# Control_Acceso_Doble_Faz.net
KiCad netlist of a schematic drawn in EAGLE
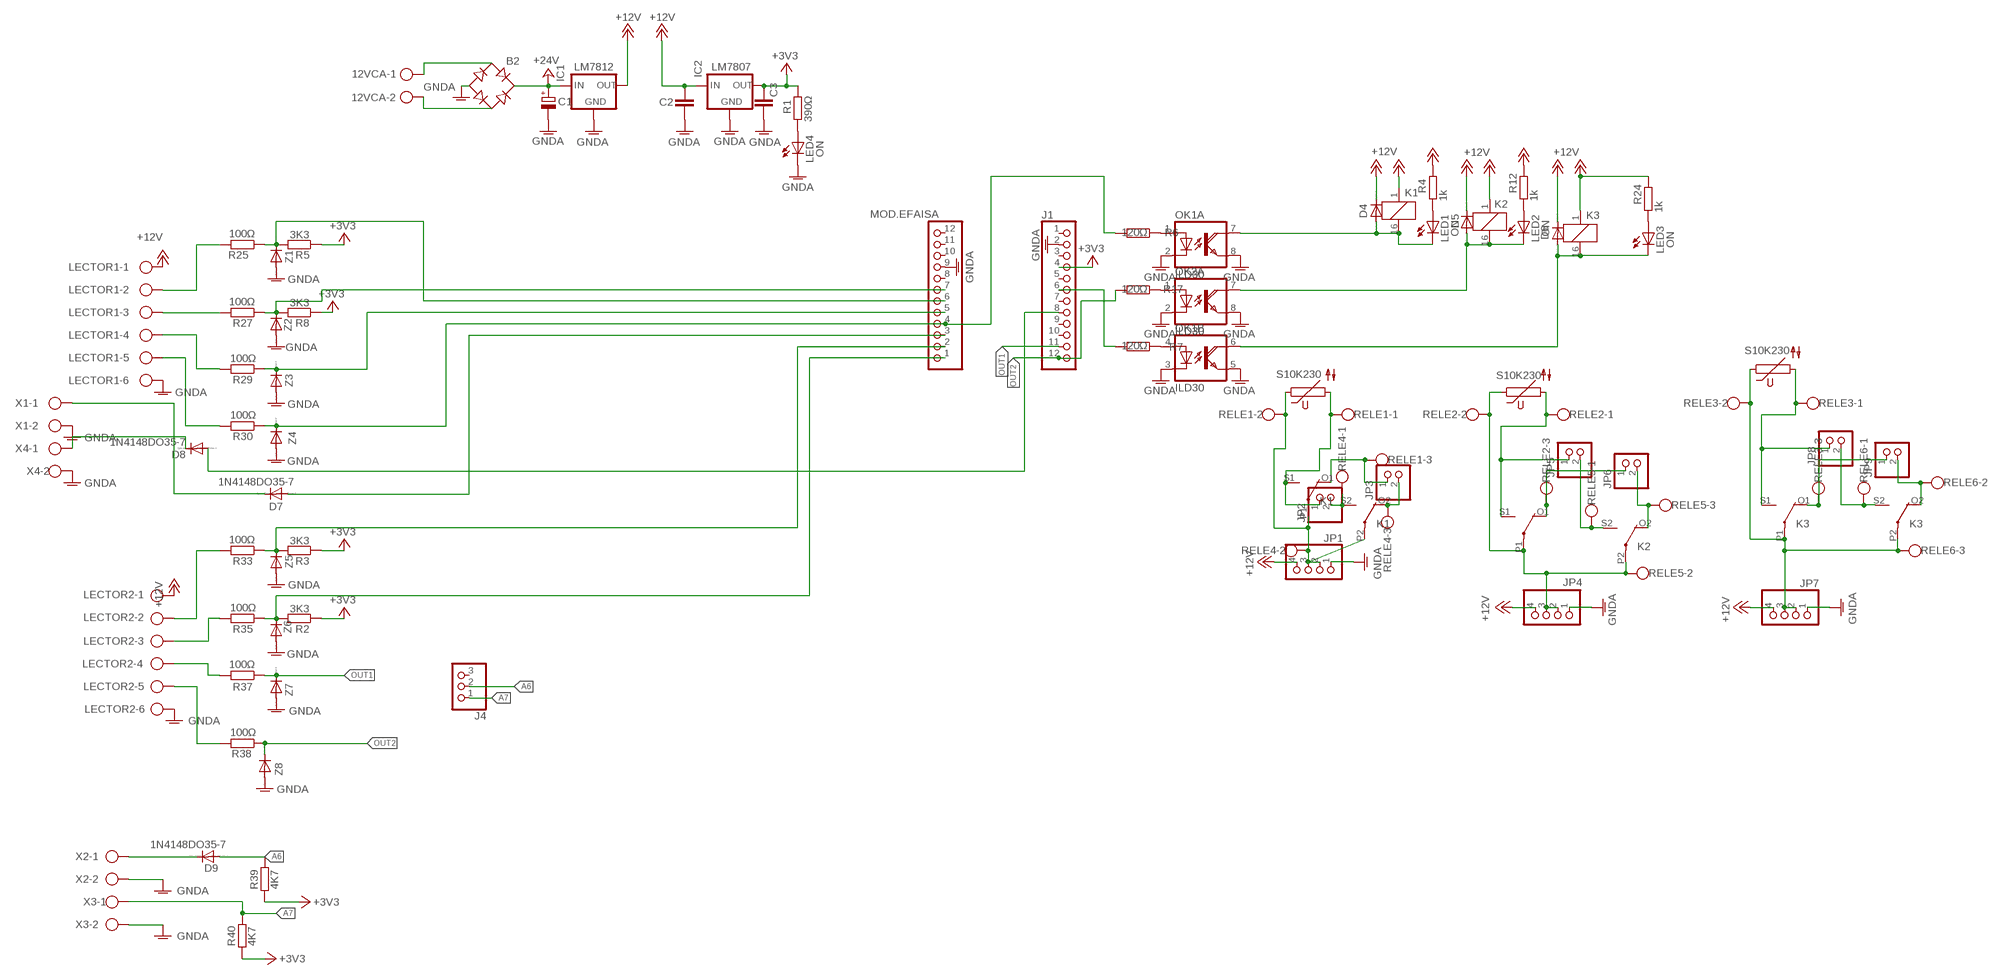
[diagram p0: schematic, sheet 1]

(export (version "E")
  (design (tool "Eeschema 10.0.6"))
  (components
    (comp (ref "12VCA")
      (value "W237-102")
      (footprint "eagle-import:W237-102")
      (fields (field (name "MPN") "237-102"))
      (libsource (lib "eagle-import") (part "W237-102"))
    )
    (comp (ref "B2")
      (value "RB1A")
      (footprint "eagle-import:RB1A")
      (libsource (lib "eagle-import") (part "RB1A"))
    )
    (comp (ref "C1")
      (value "CPOL-EUE5-13")
      (footprint "eagle-import:E5-13")
      (libsource (lib "eagle-import") (part "CPOL-EUE5-13"))
    )
    (comp (ref "C2")
      (value "C-EU050-024X044")
      (footprint "eagle-import:C050-024X044")
      (libsource (lib "eagle-import") (part "C-EU050-024X044"))
    )
    (comp (ref "C3")
      (value "C-EU050-024X044")
      (footprint "eagle-import:C050-024X044")
      (libsource (lib "eagle-import") (part "C-EU050-024X044"))
    )
    (comp (ref "D4")
      (value "1N4148DO35-7")
      (footprint "eagle-import:DO35-7")
      (libsource (lib "eagle-import") (part "1N4148DO35-7"))
    )
    (comp (ref "D5")
      (value "1N4148DO35-7")
      (footprint "eagle-import:DO35-7")
      (libsource (lib "eagle-import") (part "1N4148DO35-7"))
    )
    (comp (ref "D6")
      (value "1N4148DO35-7")
      (footprint "eagle-import:DO35-7")
      (libsource (lib "eagle-import") (part "1N4148DO35-7"))
    )
    (comp (ref "D7")
      (value "1N4148DO35-7")
      (footprint "eagle-import:DO35-7")
      (libsource (lib "eagle-import") (part "1N4148DO35-7"))
    )
    (comp (ref "D8")
      (value "1N4148DO35-7")
      (footprint "eagle-import:DO35-7")
      (libsource (lib "eagle-import") (part "1N4148DO35-7"))
    )
    (comp (ref "D9")
      (value "1N4148DO35-7")
      (footprint "eagle-import:DO35-7")
      (libsource (lib "eagle-import") (part "1N4148DO35-7"))
    )
    (comp (ref "IC1")
      (value "LM7812")
      (footprint "eagle-import:78XXS")
      (libsource (lib "eagle-import") (part "78XXS"))
    )
    (comp (ref "IC2")
      (value "LM7807")
      (footprint "eagle-import:78XXS")
      (libsource (lib "eagle-import") (part "78XXS"))
    )
    (comp (ref "J1")
      (value "PINHD-1X12")
      (footprint "eagle-import:1X12")
      (libsource (lib "eagle-import") (part "PINHD-1X12"))
    )
    (comp (ref "J4")
      (value "PINHD-1X3")
      (footprint "eagle-import:1X03")
      (libsource (lib "eagle-import") (part "PINHD-1X3"))
    )
    (comp (ref "JP1")
      (value "PINHD-1X4")
      (footprint "eagle-import:1X04")
      (libsource (lib "eagle-import") (part "PINHD-1X4"))
    )
    (comp (ref "JP2")
      (value "PINHD-1X2")
      (footprint "eagle-import:1X02")
      (libsource (lib "eagle-import") (part "PINHD-1X2"))
    )
    (comp (ref "JP3")
      (value "PINHD-1X2")
      (footprint "eagle-import:1X02")
      (libsource (lib "eagle-import") (part "PINHD-1X2"))
    )
    (comp (ref "JP4")
      (value "PINHD-1X4")
      (footprint "eagle-import:1X04")
      (libsource (lib "eagle-import") (part "PINHD-1X4"))
    )
    (comp (ref "JP5")
      (value "PINHD-1X2")
      (footprint "eagle-import:1X02")
      (libsource (lib "eagle-import") (part "PINHD-1X2"))
    )
    (comp (ref "JP6")
      (value "PINHD-1X2")
      (footprint "eagle-import:1X02")
      (libsource (lib "eagle-import") (part "PINHD-1X2"))
    )
    (comp (ref "JP7")
      (value "PINHD-1X4")
      (footprint "eagle-import:1X04")
      (libsource (lib "eagle-import") (part "PINHD-1X4"))
    )
    (comp (ref "JP8")
      (value "PINHD-1X2")
      (footprint "eagle-import:1X02")
      (libsource (lib "eagle-import") (part "PINHD-1X2"))
    )
    (comp (ref "JP9")
      (value "PINHD-1X2")
      (footprint "eagle-import:1X02")
      (libsource (lib "eagle-import") (part "PINHD-1X2"))
    )
    (comp (ref "K1")
      (value "351")
      (footprint "eagle-import:351")
      (libsource (lib "eagle-import") (part "351"))
    )
    (comp (ref "K2")
      (value "351")
      (footprint "eagle-import:351")
      (libsource (lib "eagle-import") (part "351"))
    )
    (comp (ref "K3")
      (value "351")
      (footprint "eagle-import:351")
      (libsource (lib "eagle-import") (part "351"))
    )
    (comp (ref "LECTOR1")
      (value "W237-6")
      (footprint "eagle-import:W237-6")
      (libsource (lib "eagle-import") (part "W237-6"))
    )
    (comp (ref "LECTOR2")
      (value "W237-6")
      (footprint "eagle-import:W237-6")
      (libsource (lib "eagle-import") (part "W237-6"))
    )
    (comp (ref "LED1")
      (value "ON")
      (footprint "eagle-import:LED3MM")
      (libsource (lib "eagle-import") (part "LED3MM"))
    )
    (comp (ref "LED2")
      (value "ON")
      (footprint "eagle-import:LED3MM")
      (libsource (lib "eagle-import") (part "LED3MM"))
    )
    (comp (ref "LED3")
      (value "ON")
      (footprint "eagle-import:LED3MM")
      (libsource (lib "eagle-import") (part "LED3MM"))
    )
    (comp (ref "LED4")
      (value "ON")
      (footprint "eagle-import:LED3MM")
      (libsource (lib "eagle-import") (part "LED3MM"))
    )
    (comp (ref "MOD.EFAISA")
      (value "PINHD-1X12")
      (footprint "eagle-import:1X12")
      (libsource (lib "eagle-import") (part "PINHD-1X12"))
    )
    (comp (ref "OK1")
      (value "ILD30")
      (footprint "eagle-import:DIL08")
      (fields (field (name "MF") "VISHAY/TELEFUNKEN"))
      (libsource (lib "eagle-import") (part "ILD30"))
    )
    (comp (ref "OK2")
      (value "ILD30")
      (footprint "eagle-import:DIL08")
      (fields (field (name "MF") "VISHAY/TELEFUNKEN"))
      (libsource (lib "eagle-import") (part "ILD30"))
    )
    (comp (ref "R1")
      (value "390Ω")
      (footprint "eagle-import:0204_7")
      (libsource (lib "eagle-import") (part "R-EU_0204/7"))
    )
    (comp (ref "R2")
      (value "3K3")
      (footprint "eagle-import:0204_7")
      (libsource (lib "eagle-import") (part "R-EU_0204/7"))
    )
    (comp (ref "R3")
      (value "3K3")
      (footprint "eagle-import:0204_7")
      (libsource (lib "eagle-import") (part "R-EU_0204/7"))
    )
    (comp (ref "R4")
      (value "1k")
      (footprint "eagle-import:0204_7")
      (libsource (lib "eagle-import") (part "R-EU_0204/7"))
    )
    (comp (ref "R5")
      (value "3K3")
      (footprint "eagle-import:0204_7")
      (libsource (lib "eagle-import") (part "R-EU_0204/7"))
    )
    (comp (ref "R6")
      (value "120Ω")
      (footprint "eagle-import:0204_7")
      (libsource (lib "eagle-import") (part "R-EU_0204/7"))
    )
    (comp (ref "R7")
      (value "120Ω")
      (footprint "eagle-import:0204_7")
      (libsource (lib "eagle-import") (part "R-EU_0204/7"))
    )
    (comp (ref "R8")
      (value "3K3")
      (footprint "eagle-import:0204_7")
      (libsource (lib "eagle-import") (part "R-EU_0204/7"))
    )
    (comp (ref "R12")
      (value "1k")
      (footprint "eagle-import:0204_7")
      (libsource (lib "eagle-import") (part "R-EU_0204/7"))
    )
    (comp (ref "R17")
      (value "120Ω")
      (footprint "eagle-import:0204_7")
      (libsource (lib "eagle-import") (part "R-EU_0204/7"))
    )
    (comp (ref "R24")
      (value "1k")
      (footprint "eagle-import:0204_7")
      (libsource (lib "eagle-import") (part "R-EU_0204/7"))
    )
    (comp (ref "R25")
      (value "100Ω")
      (footprint "eagle-import:0204_7")
      (libsource (lib "eagle-import") (part "R-EU_0204/7"))
    )
    (comp (ref "R27")
      (value "100Ω")
      (footprint "eagle-import:0204_7")
      (libsource (lib "eagle-import") (part "R-EU_0204/7"))
    )
    (comp (ref "R29")
      (value "100Ω")
      (footprint "eagle-import:0204_7")
      (libsource (lib "eagle-import") (part "R-EU_0204/7"))
    )
    (comp (ref "R30")
      (value "100Ω")
      (footprint "eagle-import:0204_7")
      (libsource (lib "eagle-import") (part "R-EU_0204/7"))
    )
    (comp (ref "R33")
      (value "100Ω")
      (footprint "eagle-import:0204_7")
      (libsource (lib "eagle-import") (part "R-EU_0204/7"))
    )
    (comp (ref "R35")
      (value "100Ω")
      (footprint "eagle-import:0204_7")
      (libsource (lib "eagle-import") (part "R-EU_0204/7"))
    )
    (comp (ref "R37")
      (value "100Ω")
      (footprint "eagle-import:0204_7")
      (libsource (lib "eagle-import") (part "R-EU_0204/7"))
    )
    (comp (ref "R38")
      (value "100Ω")
      (footprint "eagle-import:0204_7")
      (libsource (lib "eagle-import") (part "R-EU_0204/7"))
    )
    (comp (ref "R39")
      (value "4K7")
      (footprint "eagle-import:0204_7")
      (libsource (lib "eagle-import") (part "R-EU_0204/7"))
    )
    (comp (ref "R40")
      (value "4K7")
      (footprint "eagle-import:0204_7")
      (libsource (lib "eagle-import") (part "R-EU_0204/7"))
    )
    (comp (ref "RELE1")
      (value "W237-103")
      (footprint "eagle-import:W237-103")
      (fields (field (name "MPN") "237-103"))
      (libsource (lib "eagle-import") (part "W237-103"))
    )
    (comp (ref "RELE2")
      (value "W237-103")
      (footprint "eagle-import:W237-103")
      (fields (field (name "MPN") "237-103"))
      (libsource (lib "eagle-import") (part "W237-103"))
    )
    (comp (ref "RELE3")
      (value "W237-103")
      (footprint "eagle-import:W237-103")
      (fields (field (name "MPN") "237-103"))
      (libsource (lib "eagle-import") (part "W237-103"))
    )
    (comp (ref "RELE4")
      (value "W237-103")
      (footprint "eagle-import:W237-103")
      (fields (field (name "MPN") "237-103"))
      (libsource (lib "eagle-import") (part "W237-103"))
    )
    (comp (ref "RELE5")
      (value "W237-103")
      (footprint "eagle-import:W237-103")
      (fields (field (name "MPN") "237-103"))
      (libsource (lib "eagle-import") (part "W237-103"))
    )
    (comp (ref "RELE6")
      (value "W237-103")
      (footprint "eagle-import:W237-103")
      (fields (field (name "MPN") "237-103"))
      (libsource (lib "eagle-import") (part "W237-103"))
    )
    (comp (ref "V1")
      (value "S10K230")
      (footprint "eagle-import:S10K230")
      (libsource (lib "eagle-import") (part "S10K230"))
    )
    (comp (ref "V2")
      (value "S10K230")
      (footprint "eagle-import:S10K230")
      (libsource (lib "eagle-import") (part "S10K230"))
    )
    (comp (ref "V3")
      (value "S10K230")
      (footprint "eagle-import:S10K230")
      (libsource (lib "eagle-import") (part "S10K230"))
    )
    (comp (ref "X1")
      (value "W237-102")
      (footprint "eagle-import:W237-102")
      (fields (field (name "MPN") "237-102"))
      (libsource (lib "eagle-import") (part "W237-102"))
    )
    (comp (ref "X2")
      (value "W237-102")
      (footprint "eagle-import:W237-102")
      (fields (field (name "MPN") "237-102"))
      (libsource (lib "eagle-import") (part "W237-102"))
    )
    (comp (ref "X3")
      (value "W237-102")
      (footprint "eagle-import:W237-102")
      (fields (field (name "MPN") "237-102"))
      (libsource (lib "eagle-import") (part "W237-102"))
    )
    (comp (ref "X4")
      (value "W237-102")
      (footprint "eagle-import:W237-102")
      (fields (field (name "MPN") "237-102"))
      (libsource (lib "eagle-import") (part "W237-102"))
    )
    (comp (ref "Z1")
      (value "ZENNER 4V7")
      (footprint "eagle-import:DO35-7")
      (libsource (lib "eagle-import") (part "1N4148DO35-7"))
    )
    (comp (ref "Z2")
      (value "ZENNER 4V7")
      (footprint "eagle-import:DO35-7")
      (libsource (lib "eagle-import") (part "1N4148DO35-7"))
    )
    (comp (ref "Z3")
      (value "ZENNER 4V7")
      (footprint "eagle-import:DO35-7")
      (libsource (lib "eagle-import") (part "1N4148DO35-7"))
    )
    (comp (ref "Z4")
      (value "ZENNER 4V7")
      (footprint "eagle-import:DO35-7")
      (libsource (lib "eagle-import") (part "1N4148DO35-7"))
    )
    (comp (ref "Z5")
      (value "ZENNER 4V7")
      (footprint "eagle-import:DO35-7")
      (libsource (lib "eagle-import") (part "1N4148DO35-7"))
    )
    (comp (ref "Z6")
      (value "ZENNER 4V7")
      (footprint "eagle-import:DO35-7")
      (libsource (lib "eagle-import") (part "1N4148DO35-7"))
    )
    (comp (ref "Z7")
      (value "ZENNER 4V7")
      (footprint "eagle-import:DO35-7")
      (libsource (lib "eagle-import") (part "1N4148DO35-7"))
    )
    (comp (ref "Z8")
      (value "ZENNER 4V7")
      (footprint "eagle-import:DO35-7")
      (libsource (lib "eagle-import") (part "1N4148DO35-7"))
    )
  )
  (nets
    (net (code "1") (name "+3V3") (class "Default")
      (node (ref "C3") (pin "1") (pinfunction "1_1") (pintype "passive"))
      (node (ref "IC2") (pin "OUT") (pinfunction "OUT_OUT") (pintype "passive"))
      (node (ref "J1") (pin "4") (pinfunction "4_4") (pintype "passive"))
      (node (ref "R1") (pin "2") (pinfunction "2_2") (pintype "passive"))
      (node (ref "R2") (pin "1") (pinfunction "1_1") (pintype "passive"))
      (node (ref "R3") (pin "1") (pinfunction "1_1") (pintype "passive"))
      (node (ref "R39") (pin "1") (pinfunction "1_1") (pintype "passive"))
      (node (ref "R40") (pin "1") (pinfunction "1_1") (pintype "passive"))
      (node (ref "R5") (pin "1") (pinfunction "1_1") (pintype "passive"))
      (node (ref "R8") (pin "1") (pinfunction "1_1") (pintype "passive"))
    )
    (net (code "2") (name "+12V") (class "Default")
      (node (ref "C2") (pin "1") (pinfunction "1_1") (pintype "passive"))
      (node (ref "D4") (pin "C") (pinfunction "C_C") (pintype "passive"))
      (node (ref "D5") (pin "C") (pinfunction "C_C") (pintype "passive"))
      (node (ref "D6") (pin "C") (pinfunction "C_C") (pintype "passive"))
      (node (ref "IC1") (pin "OUT") (pinfunction "OUT_OUT") (pintype "passive"))
      (node (ref "IC2") (pin "IN") (pinfunction "IN_IN") (pintype "input"))
      (node (ref "JP1") (pin "4") (pinfunction "4_4") (pintype "passive"))
      (node (ref "JP4") (pin "4") (pinfunction "4_4") (pintype "passive"))
      (node (ref "JP7") (pin "4") (pinfunction "4_4") (pintype "passive"))
      (node (ref "K1") (pin "1") (pinfunction "1_1") (pintype "passive"))
      (node (ref "K2") (pin "1") (pinfunction "1_1") (pintype "passive"))
      (node (ref "K3") (pin "1") (pinfunction "1_1") (pintype "passive"))
      (node (ref "LECTOR1") (pin "1") (pinfunction "KL_1") (pintype "passive"))
      (node (ref "LECTOR2") (pin "1") (pinfunction "KL_1") (pintype "passive"))
      (node (ref "R12") (pin "2") (pinfunction "2_2") (pintype "passive"))
      (node (ref "R24") (pin "2") (pinfunction "2_2") (pintype "passive"))
      (node (ref "R4") (pin "2") (pinfunction "2_2") (pintype "passive"))
    )
    (net (code "3") (name "+24V") (class "Default")
      (node (ref "B2") (pin "+") (pinfunction "+_+") (pintype "passive"))
      (node (ref "C1") (pin "+") (pinfunction "+_+") (pintype "passive"))
      (node (ref "IC1") (pin "IN") (pinfunction "IN_IN") (pintype "input"))
    )
    (net (code "4") (name "A6") (class "Default")
      (node (ref "D9") (pin "A") (pinfunction "A_A") (pintype "passive"))
      (node (ref "J4") (pin "2") (pinfunction "2_2") (pintype "passive"))
      (node (ref "R39") (pin "2") (pinfunction "2_2") (pintype "passive"))
    )
    (net (code "5") (name "A7") (class "Default")
      (node (ref "J4") (pin "1") (pinfunction "1_1") (pintype "passive"))
      (node (ref "R40") (pin "2") (pinfunction "2_2") (pintype "passive"))
      (node (ref "X3") (pin "1") (pinfunction "KL_1") (pintype "passive"))
    )
    (net (code "6") (name "GNDA") (class "Default")
      (node (ref "B2") (pin "-") (pinfunction "-_-") (pintype "passive"))
      (node (ref "C1") (pin "-") (pinfunction "-_-") (pintype "passive"))
      (node (ref "C2") (pin "2") (pinfunction "2_2") (pintype "passive"))
      (node (ref "C3") (pin "2") (pinfunction "2_2") (pintype "passive"))
      (node (ref "IC1") (pin "GND") (pinfunction "GND_GND") (pintype "input"))
      (node (ref "IC2") (pin "GND") (pinfunction "GND_GND") (pintype "input"))
      (node (ref "J1") (pin "2") (pinfunction "2_2") (pintype "passive"))
      (node (ref "JP1") (pin "1") (pinfunction "1_1") (pintype "passive"))
      (node (ref "JP4") (pin "1") (pinfunction "1_1") (pintype "passive"))
      (node (ref "JP7") (pin "1") (pinfunction "1_1") (pintype "passive"))
      (node (ref "LECTOR1") (pin "6") (pinfunction "KL_6") (pintype "passive"))
      (node (ref "LECTOR2") (pin "6") (pinfunction "KL_6") (pintype "passive"))
      (node (ref "LED4") (pin "K") (pinfunction "C_K") (pintype "passive"))
      (node (ref "MOD.EFAISA") (pin "9") (pinfunction "9_9") (pintype "passive"))
      (node (ref "OK1") (pin "2") (pinfunction "C_2") (pintype "passive"))
      (node (ref "OK1") (pin "3") (pinfunction "C_3") (pintype "passive"))
      (node (ref "OK1") (pin "5") (pinfunction "EMI_5") (pintype "passive"))
      (node (ref "OK1") (pin "8") (pinfunction "EMI_8") (pintype "passive"))
      (node (ref "OK2") (pin "2") (pinfunction "C_2") (pintype "passive"))
      (node (ref "OK2") (pin "8") (pinfunction "EMI_8") (pintype "passive"))
      (node (ref "X1") (pin "2") (pinfunction "KL_2") (pintype "passive"))
      (node (ref "X2") (pin "2") (pinfunction "KL_2") (pintype "passive"))
      (node (ref "X3") (pin "2") (pinfunction "KL_2") (pintype "passive"))
      (node (ref "X4") (pin "2") (pinfunction "KL_2") (pintype "passive"))
      (node (ref "Z1") (pin "A") (pinfunction "A_A") (pintype "passive"))
      (node (ref "Z2") (pin "A") (pinfunction "A_A") (pintype "passive"))
      (node (ref "Z3") (pin "A") (pinfunction "A_A") (pintype "passive"))
      (node (ref "Z4") (pin "A") (pinfunction "A_A") (pintype "passive"))
      (node (ref "Z5") (pin "A") (pinfunction "A_A") (pintype "passive"))
      (node (ref "Z6") (pin "A") (pinfunction "A_A") (pintype "passive"))
      (node (ref "Z7") (pin "A") (pinfunction "A_A") (pintype "passive"))
      (node (ref "Z8") (pin "A") (pinfunction "A_A") (pintype "passive"))
    )
    (net (code "7") (name "Net-(12VCAA-KL)") (class "Default")
      (node (ref "12VCA") (pin "1") (pinfunction "KL_1") (pintype "passive"))
      (node (ref "B2") (pin "AC1") (pinfunction "AC1_AC1") (pintype "passive"))
    )
    (net (code "8") (name "Net-(12VCAB-KL)") (class "Default")
      (node (ref "12VCA") (pin "2") (pinfunction "KL_2") (pintype "passive"))
      (node (ref "B2") (pin "AC2") (pinfunction "AC2_AC2") (pintype "passive"))
    )
    (net (code "9") (name "Net-(D7-PadA)") (class "Default")
      (node (ref "D7") (pin "A") (pinfunction "A_A") (pintype "passive"))
      (node (ref "MOD.EFAISA") (pin "3") (pinfunction "3_3") (pintype "passive"))
    )
    (net (code "10") (name "Net-(D8-PadA)") (class "Default")
      (node (ref "D8") (pin "A") (pinfunction "A_A") (pintype "passive"))
      (node (ref "J1") (pin "8") (pinfunction "8_8") (pintype "passive"))
    )
    (net (code "11") (name "Net-(J1-Pad6)") (class "Default")
      (node (ref "J1") (pin "6") (pinfunction "6_6") (pintype "passive"))
      (node (ref "R7") (pin "2") (pinfunction "2_2") (pintype "passive"))
    )
    (net (code "12") (name "Net-(K1A-2)") (class "Default")
      (node (ref "D4") (pin "A") (pinfunction "A_A") (pintype "passive"))
      (node (ref "K1") (pin "16") (pinfunction "2_16") (pintype "passive"))
      (node (ref "LED1") (pin "K") (pinfunction "C_K") (pintype "passive"))
      (node (ref "OK1") (pin "7") (pinfunction "COL_7") (pintype "passive"))
    )
    (net (code "13") (name "Net-(K1B-O)") (class "Default")
      (node (ref "JP3") (pin "1") (pinfunction "1_1") (pintype "passive"))
      (node (ref "K1") (pin "O1") (pinfunction "O_O1") (pintype "passive"))
      (node (ref "RELE1") (pin "3") (pinfunction "KL_3") (pintype "passive"))
    )
    (net (code "14") (name "Net-(K1B-P)") (class "Default")
      (node (ref "JP1") (pin "2") (pinfunction "2_2") (pintype "passive"))
      (node (ref "JP1") (pin "3") (pinfunction "3_3") (pintype "passive"))
      (node (ref "K1") (pin "P1") (pinfunction "P_P1") (pintype "passive"))
      (node (ref "K1") (pin "P2") (pinfunction "P_P2") (pintype "passive"))
      (node (ref "RELE1") (pin "2") (pinfunction "KL_2") (pintype "passive"))
      (node (ref "RELE4") (pin "2") (pinfunction "KL_2") (pintype "passive"))
      (node (ref "V1") (pin "1") (pinfunction "1_1") (pintype "passive"))
    )
    (net (code "15") (name "Net-(K1B-S)") (class "Default")
      (node (ref "JP2") (pin "1") (pinfunction "1_1") (pintype "passive"))
      (node (ref "K1") (pin "S1") (pinfunction "S_S1") (pintype "passive"))
      (node (ref "RELE1") (pin "1") (pinfunction "KL_1") (pintype "passive"))
      (node (ref "V1") (pin "2") (pinfunction "2_2") (pintype "passive"))
    )
    (net (code "16") (name "Net-(K1C-O)") (class "Default")
      (node (ref "JP3") (pin "2") (pinfunction "2_2") (pintype "passive"))
      (node (ref "K1") (pin "O2") (pinfunction "O_O2") (pintype "passive"))
      (node (ref "RELE4") (pin "3") (pinfunction "KL_3") (pintype "passive"))
    )
    (net (code "17") (name "Net-(K1C-S)") (class "Default")
      (node (ref "JP2") (pin "2") (pinfunction "2_2") (pintype "passive"))
      (node (ref "K1") (pin "S2") (pinfunction "S_S2") (pintype "passive"))
      (node (ref "RELE4") (pin "1") (pinfunction "KL_1") (pintype "passive"))
    )
    (net (code "18") (name "Net-(K2A-2)") (class "Default")
      (node (ref "D5") (pin "A") (pinfunction "A_A") (pintype "passive"))
      (node (ref "K2") (pin "16") (pinfunction "2_16") (pintype "passive"))
      (node (ref "LED2") (pin "K") (pinfunction "C_K") (pintype "passive"))
      (node (ref "OK2") (pin "7") (pinfunction "COL_7") (pintype "passive"))
    )
    (net (code "19") (name "Net-(K2B-O)") (class "Default")
      (node (ref "JP6") (pin "1") (pinfunction "1_1") (pintype "passive"))
      (node (ref "K2") (pin "O1") (pinfunction "O_O1") (pintype "passive"))
      (node (ref "RELE2") (pin "3") (pinfunction "KL_3") (pintype "passive"))
    )
    (net (code "20") (name "Net-(K2B-P)") (class "Default")
      (node (ref "JP4") (pin "2") (pinfunction "2_2") (pintype "passive"))
      (node (ref "JP4") (pin "3") (pinfunction "3_3") (pintype "passive"))
      (node (ref "K2") (pin "P1") (pinfunction "P_P1") (pintype "passive"))
      (node (ref "K2") (pin "P2") (pinfunction "P_P2") (pintype "passive"))
      (node (ref "RELE2") (pin "2") (pinfunction "KL_2") (pintype "passive"))
      (node (ref "RELE5") (pin "2") (pinfunction "KL_2") (pintype "passive"))
      (node (ref "V2") (pin "1") (pinfunction "1_1") (pintype "passive"))
    )
    (net (code "21") (name "Net-(K2B-S)") (class "Default")
      (node (ref "JP5") (pin "1") (pinfunction "1_1") (pintype "passive"))
      (node (ref "K2") (pin "S1") (pinfunction "S_S1") (pintype "passive"))
      (node (ref "RELE2") (pin "1") (pinfunction "KL_1") (pintype "passive"))
      (node (ref "V2") (pin "2") (pinfunction "2_2") (pintype "passive"))
    )
    (net (code "22") (name "Net-(K2C-O)") (class "Default")
      (node (ref "JP6") (pin "2") (pinfunction "2_2") (pintype "passive"))
      (node (ref "K2") (pin "O2") (pinfunction "O_O2") (pintype "passive"))
      (node (ref "RELE5") (pin "3") (pinfunction "KL_3") (pintype "passive"))
    )
    (net (code "23") (name "Net-(K2C-S)") (class "Default")
      (node (ref "JP5") (pin "2") (pinfunction "2_2") (pintype "passive"))
      (node (ref "K2") (pin "S2") (pinfunction "S_S2") (pintype "passive"))
      (node (ref "RELE5") (pin "1") (pinfunction "KL_1") (pintype "passive"))
    )
    (net (code "24") (name "Net-(K3A-2)") (class "Default")
      (node (ref "D6") (pin "A") (pinfunction "A_A") (pintype "passive"))
      (node (ref "K3") (pin "16") (pinfunction "2_16") (pintype "passive"))
      (node (ref "LED3") (pin "K") (pinfunction "C_K") (pintype "passive"))
      (node (ref "OK1") (pin "6") (pinfunction "COL_6") (pintype "passive"))
    )
    (net (code "25") (name "Net-(K3B-O)") (class "Default")
      (node (ref "JP9") (pin "1") (pinfunction "1_1") (pintype "passive"))
      (node (ref "K3") (pin "O1") (pinfunction "O_O1") (pintype "passive"))
      (node (ref "RELE3") (pin "3") (pinfunction "KL_3") (pintype "passive"))
    )
    (net (code "26") (name "Net-(K3B-P)") (class "Default")
      (node (ref "JP7") (pin "2") (pinfunction "2_2") (pintype "passive"))
      (node (ref "JP7") (pin "3") (pinfunction "3_3") (pintype "passive"))
      (node (ref "K3") (pin "P1") (pinfunction "P_P1") (pintype "passive"))
      (node (ref "K3") (pin "P2") (pinfunction "P_P2") (pintype "passive"))
      (node (ref "RELE3") (pin "2") (pinfunction "KL_2") (pintype "passive"))
      (node (ref "RELE6") (pin "3") (pinfunction "KL_3") (pintype "passive"))
      (node (ref "V3") (pin "1") (pinfunction "1_1") (pintype "passive"))
    )
    (net (code "27") (name "Net-(K3B-S)") (class "Default")
      (node (ref "JP8") (pin "1") (pinfunction "1_1") (pintype "passive"))
      (node (ref "K3") (pin "S1") (pinfunction "S_S1") (pintype "passive"))
      (node (ref "RELE3") (pin "1") (pinfunction "KL_1") (pintype "passive"))
      (node (ref "V3") (pin "2") (pinfunction "2_2") (pintype "passive"))
    )
    (net (code "28") (name "Net-(K3C-O)") (class "Default")
      (node (ref "JP9") (pin "2") (pinfunction "2_2") (pintype "passive"))
      (node (ref "K3") (pin "O2") (pinfunction "O_O2") (pintype "passive"))
      (node (ref "RELE6") (pin "2") (pinfunction "KL_2") (pintype "passive"))
    )
    (net (code "29") (name "Net-(K3C-S)") (class "Default")
      (node (ref "JP8") (pin "2") (pinfunction "2_2") (pintype "passive"))
      (node (ref "K3") (pin "S2") (pinfunction "S_S2") (pintype "passive"))
      (node (ref "RELE6") (pin "1") (pinfunction "KL_1") (pintype "passive"))
    )
    (net (code "30") (name "Net-(LECTOR1B-KL)") (class "Default")
      (node (ref "LECTOR1") (pin "2") (pinfunction "KL_2") (pintype "passive"))
      (node (ref "R25") (pin "2") (pinfunction "2_2") (pintype "passive"))
    )
    (net (code "31") (name "Net-(LECTOR1C-KL)") (class "Default")
      (node (ref "LECTOR1") (pin "3") (pinfunction "KL_3") (pintype "passive"))
      (node (ref "R27") (pin "2") (pinfunction "2_2") (pintype "passive"))
    )
    (net (code "32") (name "Net-(LECTOR1D-KL)") (class "Default")
      (node (ref "LECTOR1") (pin "4") (pinfunction "KL_4") (pintype "passive"))
      (node (ref "R29") (pin "2") (pinfunction "2_2") (pintype "passive"))
    )
    (net (code "33") (name "Net-(LECTOR1E-KL)") (class "Default")
      (node (ref "LECTOR1") (pin "5") (pinfunction "KL_5") (pintype "passive"))
      (node (ref "R30") (pin "2") (pinfunction "2_2") (pintype "passive"))
    )
    (net (code "34") (name "Net-(LECTOR2B-KL)") (class "Default")
      (node (ref "LECTOR2") (pin "2") (pinfunction "KL_2") (pintype "passive"))
      (node (ref "R33") (pin "2") (pinfunction "2_2") (pintype "passive"))
    )
    (net (code "35") (name "Net-(LECTOR2C-KL)") (class "Default")
      (node (ref "LECTOR2") (pin "3") (pinfunction "KL_3") (pintype "passive"))
      (node (ref "R35") (pin "2") (pinfunction "2_2") (pintype "passive"))
    )
    (net (code "36") (name "Net-(LECTOR2D-KL)") (class "Default")
      (node (ref "LECTOR2") (pin "4") (pinfunction "KL_4") (pintype "passive"))
      (node (ref "R37") (pin "2") (pinfunction "2_2") (pintype "passive"))
    )
    (net (code "37") (name "Net-(LECTOR2E-KL)") (class "Default")
      (node (ref "LECTOR2") (pin "5") (pinfunction "KL_5") (pintype "passive"))
      (node (ref "R38") (pin "2") (pinfunction "2_2") (pintype "passive"))
    )
    (net (code "38") (name "Net-(LED1-PadA)") (class "Default")
      (node (ref "LED1") (pin "A") (pinfunction "A_A") (pintype "passive"))
      (node (ref "R4") (pin "1") (pinfunction "1_1") (pintype "passive"))
    )
    (net (code "39") (name "Net-(LED2-PadA)") (class "Default")
      (node (ref "LED2") (pin "A") (pinfunction "A_A") (pintype "passive"))
      (node (ref "R12") (pin "1") (pinfunction "1_1") (pintype "passive"))
    )
    (net (code "40") (name "Net-(LED3-PadA)") (class "Default")
      (node (ref "LED3") (pin "A") (pinfunction "A_A") (pintype "passive"))
      (node (ref "R24") (pin "1") (pinfunction "1_1") (pintype "passive"))
    )
    (net (code "41") (name "Net-(LED4-PadA)") (class "Default")
      (node (ref "LED4") (pin "A") (pinfunction "A_A") (pintype "passive"))
      (node (ref "R1") (pin "1") (pinfunction "1_1") (pintype "passive"))
    )
    (net (code "42") (name "Net-(MOD.EFAISA-Pad1)") (class "Default")
      (node (ref "MOD.EFAISA") (pin "1") (pinfunction "1_1") (pintype "passive"))
      (node (ref "R2") (pin "2") (pinfunction "2_2") (pintype "passive"))
      (node (ref "R35") (pin "1") (pinfunction "1_1") (pintype "passive"))
      (node (ref "Z6") (pin "C") (pinfunction "C_C") (pintype "passive"))
    )
    (net (code "43") (name "Net-(MOD.EFAISA-Pad2)") (class "Default")
      (node (ref "MOD.EFAISA") (pin "2") (pinfunction "2_2") (pintype "passive"))
      (node (ref "R3") (pin "2") (pinfunction "2_2") (pintype "passive"))
      (node (ref "R33") (pin "1") (pinfunction "1_1") (pintype "passive"))
      (node (ref "Z5") (pin "C") (pinfunction "C_C") (pintype "passive"))
    )
    (net (code "44") (name "Net-(MOD.EFAISA-Pad4)") (class "Default")
      (node (ref "MOD.EFAISA") (pin "4") (pinfunction "4_4") (pintype "passive"))
      (node (ref "R30") (pin "1") (pinfunction "1_1") (pintype "passive"))
      (node (ref "R6") (pin "2") (pinfunction "2_2") (pintype "passive"))
      (node (ref "Z4") (pin "C") (pinfunction "C_C") (pintype "passive"))
    )
    (net (code "45") (name "Net-(MOD.EFAISA-Pad5)") (class "Default")
      (node (ref "MOD.EFAISA") (pin "5") (pinfunction "5_5") (pintype "passive"))
      (node (ref "R29") (pin "1") (pinfunction "1_1") (pintype "passive"))
      (node (ref "Z3") (pin "C") (pinfunction "C_C") (pintype "passive"))
    )
    (net (code "46") (name "Net-(MOD.EFAISA-Pad6)") (class "Default")
      (node (ref "MOD.EFAISA") (pin "6") (pinfunction "6_6") (pintype "passive"))
      (node (ref "R25") (pin "1") (pinfunction "1_1") (pintype "passive"))
      (node (ref "R5") (pin "2") (pinfunction "2_2") (pintype "passive"))
      (node (ref "Z1") (pin "C") (pinfunction "C_C") (pintype "passive"))
    )
    (net (code "47") (name "Net-(MOD.EFAISA-Pad7)") (class "Default")
      (node (ref "MOD.EFAISA") (pin "7") (pinfunction "7_7") (pintype "passive"))
      (node (ref "R27") (pin "1") (pinfunction "1_1") (pintype "passive"))
      (node (ref "R8") (pin "2") (pinfunction "2_2") (pintype "passive"))
      (node (ref "Z2") (pin "C") (pinfunction "C_C") (pintype "passive"))
    )
    (net (code "48") (name "Net-(OK1A-A)") (class "Default")
      (node (ref "OK1") (pin "1") (pinfunction "A_1") (pintype "passive"))
      (node (ref "R6") (pin "1") (pinfunction "1_1") (pintype "passive"))
    )
    (net (code "49") (name "Net-(OK1B-A)") (class "Default")
      (node (ref "OK1") (pin "4") (pinfunction "A_4") (pintype "passive"))
      (node (ref "R7") (pin "1") (pinfunction "1_1") (pintype "passive"))
    )
    (net (code "50") (name "Net-(OK2A-A)") (class "Default")
      (node (ref "OK2") (pin "1") (pinfunction "A_1") (pintype "passive"))
      (node (ref "R17") (pin "1") (pinfunction "1_1") (pintype "passive"))
    )
    (net (code "51") (name "Net-(X1A-KL)") (class "Default")
      (node (ref "D7") (pin "C") (pinfunction "C_C") (pintype "passive"))
      (node (ref "X1") (pin "1") (pinfunction "KL_1") (pintype "passive"))
    )
    (net (code "52") (name "Net-(X2A-KL)") (class "Default")
      (node (ref "D9") (pin "C") (pinfunction "C_C") (pintype "passive"))
      (node (ref "X2") (pin "1") (pinfunction "KL_1") (pintype "passive"))
    )
    (net (code "53") (name "Net-(X4A-KL)") (class "Default")
      (node (ref "D8") (pin "C") (pinfunction "C_C") (pintype "passive"))
      (node (ref "X4") (pin "1") (pinfunction "KL_1") (pintype "passive"))
    )
    (net (code "54") (name "OUT1") (class "Default")
      (node (ref "J1") (pin "11") (pinfunction "11_11") (pintype "passive"))
      (node (ref "R37") (pin "1") (pinfunction "1_1") (pintype "passive"))
      (node (ref "Z7") (pin "C") (pinfunction "C_C") (pintype "passive"))
    )
    (net (code "55") (name "OUT2") (class "Default")
      (node (ref "J1") (pin "12") (pinfunction "12_12") (pintype "passive"))
      (node (ref "R17") (pin "2") (pinfunction "2_2") (pintype "passive"))
      (node (ref "R38") (pin "1") (pinfunction "1_1") (pintype "passive"))
      (node (ref "Z8") (pin "C") (pinfunction "C_C") (pintype "passive"))
    )
    (net (code "56") (name "unconnected-(J1-Pad1)") (class "Default")
      (node (ref "J1") (pin "1") (pinfunction "1_1") (pintype "passive"))
    )
    (net (code "57") (name "unconnected-(J1-Pad3)") (class "Default")
      (node (ref "J1") (pin "3") (pinfunction "3_3") (pintype "passive"))
    )
    (net (code "58") (name "unconnected-(J1-Pad5)") (class "Default")
      (node (ref "J1") (pin "5") (pinfunction "5_5") (pintype "passive"))
    )
    (net (code "59") (name "unconnected-(J1-Pad7)") (class "Default")
      (node (ref "J1") (pin "7") (pinfunction "7_7") (pintype "passive"))
    )
    (net (code "60") (name "unconnected-(J1-Pad9)") (class "Default")
      (node (ref "J1") (pin "9") (pinfunction "9_9") (pintype "passive"))
    )
    (net (code "61") (name "unconnected-(J1-Pad10)") (class "Default")
      (node (ref "J1") (pin "10") (pinfunction "10_10") (pintype "passive"))
    )
    (net (code "62") (name "unconnected-(J4-Pad3)") (class "Default")
      (node (ref "J4") (pin "3") (pinfunction "3_3") (pintype "passive"))
    )
    (net (code "63") (name "unconnected-(MOD.EFAISA-Pad8)") (class "Default")
      (node (ref "MOD.EFAISA") (pin "8") (pinfunction "8_8") (pintype "passive"))
    )
    (net (code "64") (name "unconnected-(MOD.EFAISA-Pad10)") (class "Default")
      (node (ref "MOD.EFAISA") (pin "10") (pinfunction "10_10") (pintype "passive"))
    )
    (net (code "65") (name "unconnected-(MOD.EFAISA-Pad11)") (class "Default")
      (node (ref "MOD.EFAISA") (pin "11") (pinfunction "11_11") (pintype "passive"))
    )
    (net (code "66") (name "unconnected-(MOD.EFAISA-Pad12)") (class "Default")
      (node (ref "MOD.EFAISA") (pin "12") (pinfunction "12_12") (pintype "passive"))
    )
  )
)
